# mainboard.net
KiCad netlist of a schematic drawn in EAGLE
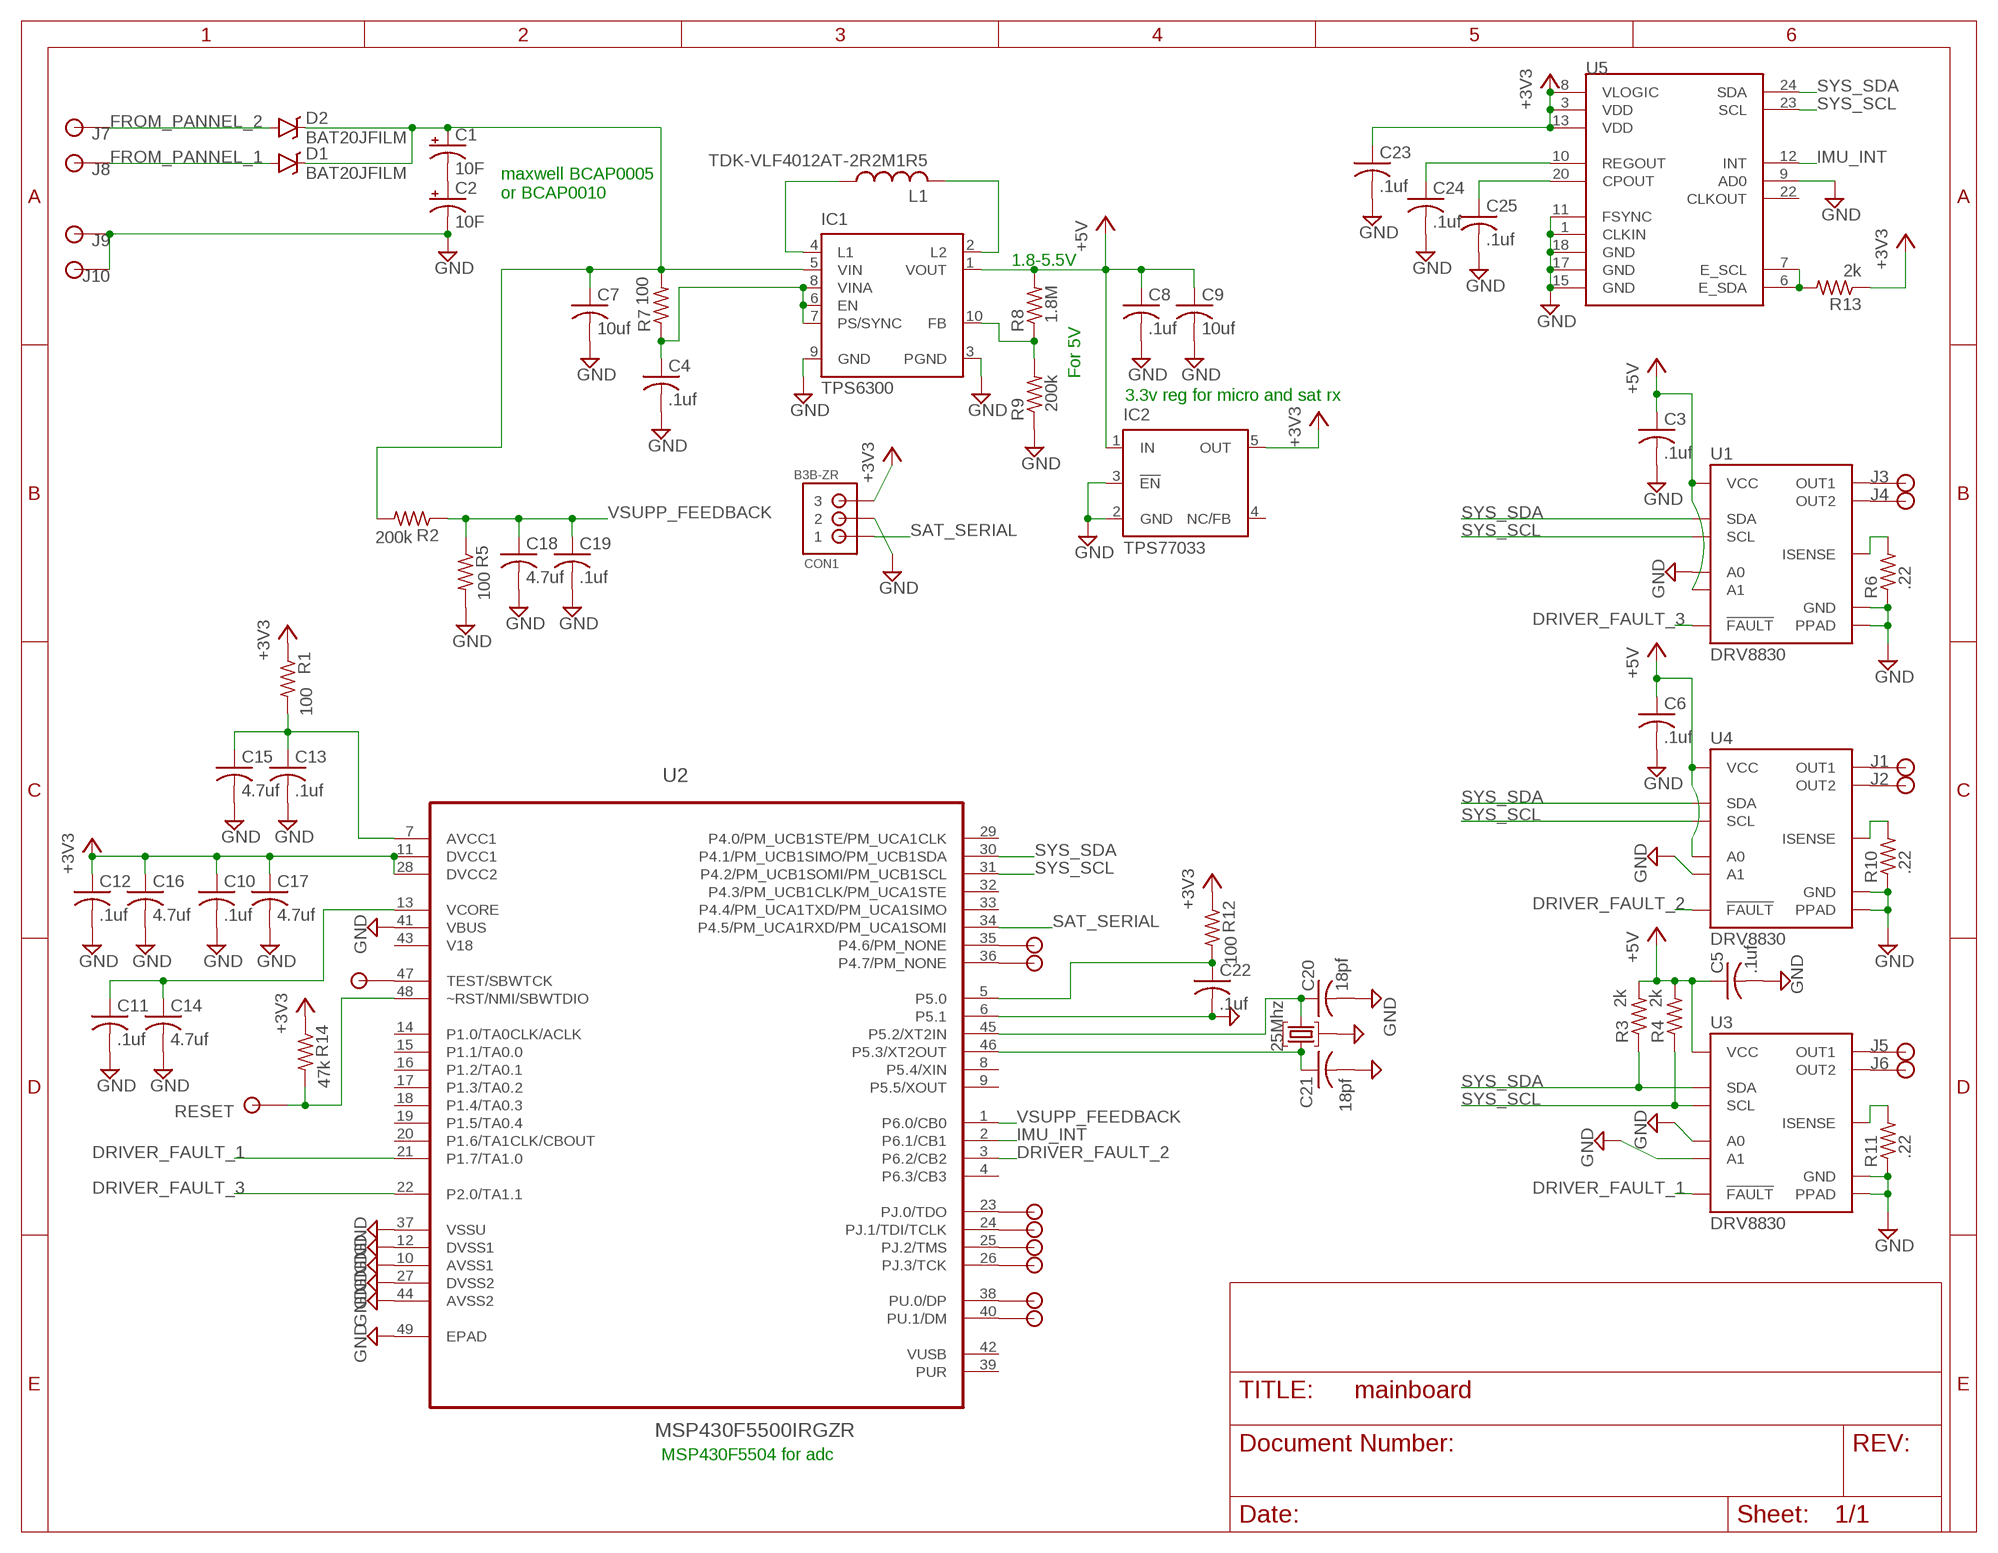
[diagram p0: schematic, sheet 1]

(export (version "E")
  (design (tool "Eeschema 10.0.6"))
  (components
    (comp (ref "C1")
      (value "10F")
      (footprint "eagle-import:E5-10,5")
      (libsource (lib "eagle-import") (part "CPOL-USE5-10.5"))
    )
    (comp (ref "C2")
      (value "10F")
      (footprint "eagle-import:E5-10,5")
      (libsource (lib "eagle-import") (part "CPOL-USE5-10.5"))
    )
    (comp (ref "C3")
      (value ".1uf")
      (footprint "eagle-import:C0603")
      (libsource (lib "eagle-import") (part "C-USC0603"))
    )
    (comp (ref "C4")
      (value ".1uf")
      (footprint "eagle-import:C0603")
      (libsource (lib "eagle-import") (part "C-USC0603"))
    )
    (comp (ref "C5")
      (value ".1uf")
      (footprint "eagle-import:C0603")
      (libsource (lib "eagle-import") (part "C-USC0603"))
    )
    (comp (ref "C6")
      (value ".1uf")
      (footprint "eagle-import:C0603")
      (libsource (lib "eagle-import") (part "C-USC0603"))
    )
    (comp (ref "C7")
      (value "10uf")
      (footprint "eagle-import:C0603")
      (libsource (lib "eagle-import") (part "C-USC0603"))
    )
    (comp (ref "C8")
      (value ".1uf")
      (footprint "eagle-import:C0603")
      (libsource (lib "eagle-import") (part "C-USC0603"))
    )
    (comp (ref "C9")
      (value "10uf")
      (footprint "eagle-import:C0603")
      (libsource (lib "eagle-import") (part "C-USC0603"))
    )
    (comp (ref "C10")
      (value ".1uf")
      (footprint "eagle-import:C0603")
      (libsource (lib "eagle-import") (part "C-USC0603"))
    )
    (comp (ref "C11")
      (value ".1uf")
      (footprint "eagle-import:C0603")
      (libsource (lib "eagle-import") (part "C-USC0603"))
    )
    (comp (ref "C12")
      (value ".1uf")
      (footprint "eagle-import:C0603")
      (libsource (lib "eagle-import") (part "C-USC0603"))
    )
    (comp (ref "C13")
      (value ".1uf")
      (footprint "eagle-import:C0603")
      (libsource (lib "eagle-import") (part "C-USC0603"))
    )
    (comp (ref "C14")
      (value "4.7uf")
      (footprint "eagle-import:C0603")
      (libsource (lib "eagle-import") (part "C-USC0603"))
    )
    (comp (ref "C15")
      (value "4.7uf")
      (footprint "eagle-import:C0603")
      (libsource (lib "eagle-import") (part "C-USC0603"))
    )
    (comp (ref "C16")
      (value "4.7uf")
      (footprint "eagle-import:C0603")
      (libsource (lib "eagle-import") (part "C-USC0603"))
    )
    (comp (ref "C17")
      (value "4.7uf")
      (footprint "eagle-import:C0603")
      (libsource (lib "eagle-import") (part "C-USC0603"))
    )
    (comp (ref "C18")
      (value "4.7uf")
      (footprint "eagle-import:C0603")
      (libsource (lib "eagle-import") (part "C-USC0603"))
    )
    (comp (ref "C19")
      (value ".1uf")
      (footprint "eagle-import:C0603")
      (libsource (lib "eagle-import") (part "C-USC0603"))
    )
    (comp (ref "C20")
      (value "18pf")
      (footprint "eagle-import:C0603")
      (libsource (lib "eagle-import") (part "C-USC0603"))
    )
    (comp (ref "C21")
      (value "18pf")
      (footprint "eagle-import:C0603")
      (libsource (lib "eagle-import") (part "C-USC0603"))
    )
    (comp (ref "C22")
      (value ".1uf")
      (footprint "eagle-import:C0603")
      (libsource (lib "eagle-import") (part "C-USC0603"))
    )
    (comp (ref "C23")
      (value ".1uf")
      (footprint "eagle-import:C0603")
      (libsource (lib "eagle-import") (part "C-USC0603"))
    )
    (comp (ref "C24")
      (value ".1uf")
      (footprint "eagle-import:C0603")
      (libsource (lib "eagle-import") (part "C-USC0603"))
    )
    (comp (ref "C25")
      (value ".1uf")
      (footprint "eagle-import:C0603")
      (libsource (lib "eagle-import") (part "C-USC0603"))
    )
    (comp (ref "CON1")
      (value "B3B-ZR")
      (footprint "eagle-import:B3B-ZR")
      (libsource (lib "eagle-import") (part "B3B-ZR"))
    )
    (comp (ref "D1")
      (value "BAT20JFILM")
      (footprint "eagle-import:SOD-323")
      (libsource (lib "eagle-import") (part "BAT20JFILM"))
    )
    (comp (ref "D2")
      (value "BAT20JFILM")
      (footprint "eagle-import:SOD-323")
      (libsource (lib "eagle-import") (part "BAT20JFILM"))
    )
    (comp (ref "IC1")
      (value "TPS6300")
      (footprint "eagle-import:DRC-S-PVSON-N10")
      (fields (field (name "MPN") "TPS63000DRCTG4"))
      (libsource (lib "eagle-import") (part "TPS6300"))
    )
    (comp (ref "IC2")
      (value "TPS77033")
      (footprint "eagle-import:SOT23-DBV")
      (fields (field (name "MF") "TEXAS INSTRUMENTS") (field (name "MPN") "TPS77033DBVT"))
      (libsource (lib "eagle-import") (part "TPS77033"))
    )
    (comp (ref "J1")
      (value "2MMPAD")
      (footprint "eagle-import:2MMPAD")
      (libsource (lib "eagle-import") (part "2MMPAD"))
    )
    (comp (ref "J2")
      (value "2MMPAD")
      (footprint "eagle-import:2MMPAD")
      (libsource (lib "eagle-import") (part "2MMPAD"))
    )
    (comp (ref "J3")
      (value "2MMPAD")
      (footprint "eagle-import:2MMPAD")
      (libsource (lib "eagle-import") (part "2MMPAD"))
    )
    (comp (ref "J4")
      (value "2MMPAD")
      (footprint "eagle-import:2MMPAD")
      (libsource (lib "eagle-import") (part "2MMPAD"))
    )
    (comp (ref "J5")
      (value "2MMPAD")
      (footprint "eagle-import:2MMPAD")
      (libsource (lib "eagle-import") (part "2MMPAD"))
    )
    (comp (ref "J6")
      (value "2MMPAD")
      (footprint "eagle-import:2MMPAD")
      (libsource (lib "eagle-import") (part "2MMPAD"))
    )
    (comp (ref "J7")
      (value "2MMPAD")
      (footprint "eagle-import:2MMPAD")
      (libsource (lib "eagle-import") (part "2MMPAD"))
    )
    (comp (ref "J8")
      (value "2MMPAD")
      (footprint "eagle-import:2MMPAD")
      (libsource (lib "eagle-import") (part "2MMPAD"))
    )
    (comp (ref "J9")
      (value "2MMPAD")
      (footprint "eagle-import:2MMPAD")
      (libsource (lib "eagle-import") (part "2MMPAD"))
    )
    (comp (ref "J10")
      (value "2MMPAD")
      (footprint "eagle-import:2MMPAD")
      (libsource (lib "eagle-import") (part "2MMPAD"))
    )
    (comp (ref "J11")
      (value "ROUND1MM")
      (footprint "eagle-import:ROUND1MM")
      (libsource (lib "eagle-import") (part "ROUND1MM"))
    )
    (comp (ref "J12")
      (value "ROUND1MM")
      (footprint "eagle-import:ROUND1MM")
      (libsource (lib "eagle-import") (part "ROUND1MM"))
    )
    (comp (ref "J13")
      (value "ROUND1MM")
      (footprint "eagle-import:ROUND1MM")
      (libsource (lib "eagle-import") (part "ROUND1MM"))
    )
    (comp (ref "J14")
      (value "ROUND1MM")
      (footprint "eagle-import:ROUND1MM")
      (libsource (lib "eagle-import") (part "ROUND1MM"))
    )
    (comp (ref "J15")
      (value "ROUND1MM")
      (footprint "eagle-import:ROUND1MM")
      (libsource (lib "eagle-import") (part "ROUND1MM"))
    )
    (comp (ref "J16")
      (value "ROUND1MM")
      (footprint "eagle-import:ROUND1MM")
      (libsource (lib "eagle-import") (part "ROUND1MM"))
    )
    (comp (ref "J17")
      (value "ROUND1MM")
      (footprint "eagle-import:ROUND1MM")
      (libsource (lib "eagle-import") (part "ROUND1MM"))
    )
    (comp (ref "J18")
      (value "ROUND1MM")
      (footprint "eagle-import:ROUND1MM")
      (libsource (lib "eagle-import") (part "ROUND1MM"))
    )
    (comp (ref "J19")
      (value "ROUND1MM")
      (footprint "eagle-import:ROUND1MM")
      (libsource (lib "eagle-import") (part "ROUND1MM"))
    )
    (comp (ref "J20")
      (value "ROUND1MM")
      (footprint "eagle-import:ROUND1MM")
      (libsource (lib "eagle-import") (part "ROUND1MM"))
    )
    (comp (ref "L1")
      (value "TDK-VLF4012AT-2R2M1R5")
      (footprint "eagle-import:TDK-VLF4012AT-2R2M1R5")
      (fields (field (name "MFG") "TDK"))
      (libsource (lib "eagle-import") (part "TDK-VLF4012AT-2R2M1R5"))
    )
    (comp (ref "Q1")
      (value "25Mhz")
      (footprint "eagle-import:SMD-3.2X2.5")
      (libsource (lib "eagle-import") (part "25MHZ-3X2MM"))
    )
    (comp (ref "R1")
      (value "100")
      (footprint "eagle-import:R0402")
      (libsource (lib "eagle-import") (part "R-US_R0402"))
    )
    (comp (ref "R2")
      (value "200k")
      (footprint "eagle-import:R0402")
      (libsource (lib "eagle-import") (part "R-US_R0402"))
    )
    (comp (ref "R3")
      (value "2k")
      (footprint "eagle-import:R0402")
      (libsource (lib "eagle-import") (part "R-US_R0402"))
    )
    (comp (ref "R4")
      (value "2k")
      (footprint "eagle-import:R0402")
      (libsource (lib "eagle-import") (part "R-US_R0402"))
    )
    (comp (ref "R5")
      (value "100")
      (footprint "eagle-import:R0402")
      (libsource (lib "eagle-import") (part "R-US_R0402"))
    )
    (comp (ref "R6")
      (value ".22")
      (footprint "eagle-import:R0402")
      (libsource (lib "eagle-import") (part "R-US_R0402"))
    )
    (comp (ref "R7")
      (value "100")
      (footprint "eagle-import:R0402")
      (libsource (lib "eagle-import") (part "R-US_R0402"))
    )
    (comp (ref "R8")
      (value "1.8M")
      (footprint "eagle-import:R0402")
      (libsource (lib "eagle-import") (part "R-US_R0402"))
    )
    (comp (ref "R9")
      (value "200k")
      (footprint "eagle-import:R0402")
      (libsource (lib "eagle-import") (part "R-US_R0402"))
    )
    (comp (ref "R10")
      (value ".22")
      (footprint "eagle-import:R0402")
      (libsource (lib "eagle-import") (part "R-US_R0402"))
    )
    (comp (ref "R11")
      (value ".22")
      (footprint "eagle-import:R0402")
      (libsource (lib "eagle-import") (part "R-US_R0402"))
    )
    (comp (ref "R12")
      (value "100")
      (footprint "eagle-import:R0402")
      (libsource (lib "eagle-import") (part "R-US_R0402"))
    )
    (comp (ref "R13")
      (value "2k")
      (footprint "eagle-import:R0402")
      (libsource (lib "eagle-import") (part "R-US_R0402"))
    )
    (comp (ref "R14")
      (value "47k")
      (footprint "eagle-import:R0402")
      (libsource (lib "eagle-import") (part "R-US_R0402"))
    )
    (comp (ref "U1")
      (value "DRV8830")
      (footprint "eagle-import:MSOP-10-GNDPAD")
      (libsource (lib "eagle-import") (part "DRV8830"))
    )
    (comp (ref "U2")
      (value "MSP430F5500IRGZR")
      (footprint "eagle-import:QFN50P700X700X100-49N")
      (libsource (lib "eagle-import") (part "MSP430F5500IRGZR"))
    )
    (comp (ref "U3")
      (value "DRV8830")
      (footprint "eagle-import:MSOP-10-GNDPAD")
      (libsource (lib "eagle-import") (part "DRV8830"))
    )
    (comp (ref "U4")
      (value "DRV8830")
      (footprint "eagle-import:MSOP-10-GNDPAD")
      (libsource (lib "eagle-import") (part "DRV8830"))
    )
    (comp (ref "U5")
      (value "MPU-9150QFN-24-NP")
      (footprint "eagle-import:QFN-24-NP")
      (libsource (lib "eagle-import") (part "MPU-9150QFN-24-NP"))
    )
  )
  (nets
    (net (code "1") (name "+3V3") (class "Default")
      (node (ref "C10") (pin "1") (pinfunction "1_1") (pintype "passive"))
      (node (ref "C12") (pin "1") (pinfunction "1_1") (pintype "passive"))
      (node (ref "C16") (pin "1") (pinfunction "1_1") (pintype "passive"))
      (node (ref "C17") (pin "1") (pinfunction "1_1") (pintype "passive"))
      (node (ref "C23") (pin "1") (pinfunction "1_1") (pintype "passive"))
      (node (ref "CON1") (pin "3") (pinfunction "3_3") (pintype "bidirectional"))
      (node (ref "IC2") (pin "5") (pinfunction "OUT_5") (pintype "passive"))
      (node (ref "R1") (pin "1") (pinfunction "1_1") (pintype "passive"))
      (node (ref "R12") (pin "1") (pinfunction "1_1") (pintype "passive"))
      (node (ref "R13") (pin "1") (pinfunction "1_1") (pintype "passive"))
      (node (ref "R14") (pin "1") (pinfunction "1_1") (pintype "passive"))
      (node (ref "U2") (pin "11") (pinfunction "DVCC1_11") (pintype "power_in"))
      (node (ref "U2") (pin "28") (pinfunction "DVCC2_28") (pintype "power_in"))
      (node (ref "U5") (pin "13") (pinfunction "VDD_13") (pintype "bidirectional"))
      (node (ref "U5") (pin "3") (pinfunction "VDD_3") (pintype "bidirectional"))
      (node (ref "U5") (pin "8") (pinfunction "VLOGIC_8") (pintype "bidirectional"))
    )
    (net (code "2") (name "+5V") (class "Default")
      (node (ref "C3") (pin "1") (pinfunction "1_1") (pintype "passive"))
      (node (ref "C5") (pin "1") (pinfunction "1_1") (pintype "passive"))
      (node (ref "C6") (pin "1") (pinfunction "1_1") (pintype "passive"))
      (node (ref "C8") (pin "1") (pinfunction "1_1") (pintype "passive"))
      (node (ref "C9") (pin "1") (pinfunction "1_1") (pintype "passive"))
      (node (ref "IC1") (pin "1") (pinfunction "VOUT_1") (pintype "output"))
      (node (ref "IC2") (pin "1") (pinfunction "IN_1") (pintype "input"))
      (node (ref "R3") (pin "2") (pinfunction "2_2") (pintype "passive"))
      (node (ref "R4") (pin "2") (pinfunction "2_2") (pintype "passive"))
      (node (ref "R8") (pin "2") (pinfunction "2_2") (pintype "passive"))
      (node (ref "U1") (pin "4") (pinfunction "VCC_4") (pintype "power_in"))
      (node (ref "U1") (pin "8") (pinfunction "A1_8") (pintype "input"))
      (node (ref "U3") (pin "4") (pinfunction "VCC_4") (pintype "power_in"))
      (node (ref "U4") (pin "4") (pinfunction "VCC_4") (pintype "power_in"))
      (node (ref "U4") (pin "7") (pinfunction "A0_7") (pintype "input"))
    )
    (net (code "3") (name "/DRIVER_FAULT_1") (class "Default")
      (node (ref "U2") (pin "21") (pinfunction "P1.7/TA1.0_21") (pintype "bidirectional"))
      (node (ref "U3") (pin "6") (pinfunction "~{FAULT}_6") (pintype "output"))
    )
    (net (code "4") (name "/DRIVER_FAULT_2") (class "Default")
      (node (ref "U2") (pin "3") (pinfunction "P6.2/CB2_3") (pintype "bidirectional"))
      (node (ref "U4") (pin "6") (pinfunction "~{FAULT}_6") (pintype "output"))
    )
    (net (code "5") (name "/DRIVER_FAULT_3") (class "Default")
      (node (ref "U1") (pin "6") (pinfunction "~{FAULT}_6") (pintype "output"))
      (node (ref "U2") (pin "22") (pinfunction "P2.0/TA1.1_22") (pintype "bidirectional"))
    )
    (net (code "6") (name "/FROM_PANNEL_1") (class "Default")
      (node (ref "D1") (pin "A") (pinfunction "A_A") (pintype "passive"))
      (node (ref "J8") (pin "P$1") (pinfunction "P$1_P$1") (pintype "bidirectional"))
    )
    (net (code "7") (name "/FROM_PANNEL_2") (class "Default")
      (node (ref "D2") (pin "A") (pinfunction "A_A") (pintype "passive"))
      (node (ref "J7") (pin "P$1") (pinfunction "P$1_P$1") (pintype "bidirectional"))
    )
    (net (code "8") (name "/IMU_INT") (class "Default")
      (node (ref "U2") (pin "2") (pinfunction "P6.1/CB1_2") (pintype "bidirectional"))
      (node (ref "U5") (pin "12") (pinfunction "INT_12") (pintype "bidirectional"))
    )
    (net (code "9") (name "/RESET") (class "Default")
      (node (ref "J15") (pin "P$1") (pinfunction "P$1_P$1") (pintype "bidirectional"))
      (node (ref "R14") (pin "2") (pinfunction "2_2") (pintype "passive"))
      (node (ref "U2") (pin "48") (pinfunction "~{RST/NMI/SBWTDIO}_48") (pintype "bidirectional"))
    )
    (net (code "10") (name "/SAT_SERIAL") (class "Default")
      (node (ref "CON1") (pin "1") (pinfunction "1_1") (pintype "bidirectional"))
      (node (ref "U2") (pin "34") (pinfunction "P4.5/PM_UCA1RXD/PM_UCA1SOMI_34") (pintype "bidirectional"))
    )
    (net (code "11") (name "/SYS_SCL") (class "Default")
      (node (ref "R4") (pin "1") (pinfunction "1_1") (pintype "passive"))
      (node (ref "U1") (pin "10") (pinfunction "SCL_10") (pintype "input"))
      (node (ref "U2") (pin "31") (pinfunction "P4.2/PM_UCB1SOMI/PM_UCB1SCL_31") (pintype "bidirectional"))
      (node (ref "U3") (pin "10") (pinfunction "SCL_10") (pintype "input"))
      (node (ref "U4") (pin "10") (pinfunction "SCL_10") (pintype "input"))
      (node (ref "U5") (pin "23") (pinfunction "SCL_23") (pintype "bidirectional"))
    )
    (net (code "12") (name "/SYS_SDA") (class "Default")
      (node (ref "R3") (pin "1") (pinfunction "1_1") (pintype "passive"))
      (node (ref "U1") (pin "9") (pinfunction "SDA_9") (pintype "bidirectional"))
      (node (ref "U2") (pin "30") (pinfunction "P4.1/PM_UCB1SIMO/PM_UCB1SDA_30") (pintype "bidirectional"))
      (node (ref "U3") (pin "9") (pinfunction "SDA_9") (pintype "bidirectional"))
      (node (ref "U4") (pin "9") (pinfunction "SDA_9") (pintype "bidirectional"))
      (node (ref "U5") (pin "24") (pinfunction "SDA_24") (pintype "bidirectional"))
    )
    (net (code "13") (name "/V18") (class "Default")
      (node (ref "U2") (pin "43") (pinfunction "V18_43") (pintype "power_in"))
    )
    (net (code "14") (name "/VSUPP_FEEDBACK") (class "Default")
      (node (ref "C18") (pin "1") (pinfunction "1_1") (pintype "passive"))
      (node (ref "C19") (pin "1") (pinfunction "1_1") (pintype "passive"))
      (node (ref "R2") (pin "1") (pinfunction "1_1") (pintype "passive"))
      (node (ref "R5") (pin "1") (pinfunction "1_1") (pintype "passive"))
      (node (ref "U2") (pin "1") (pinfunction "P6.0/CB0_1") (pintype "bidirectional"))
    )
    (net (code "15") (name "GND") (class "Default")
      (node (ref "C10") (pin "2") (pinfunction "2_2") (pintype "passive"))
      (node (ref "C11") (pin "2") (pinfunction "2_2") (pintype "passive"))
      (node (ref "C12") (pin "2") (pinfunction "2_2") (pintype "passive"))
      (node (ref "C13") (pin "2") (pinfunction "2_2") (pintype "passive"))
      (node (ref "C14") (pin "2") (pinfunction "2_2") (pintype "passive"))
      (node (ref "C15") (pin "2") (pinfunction "2_2") (pintype "passive"))
      (node (ref "C16") (pin "2") (pinfunction "2_2") (pintype "passive"))
      (node (ref "C17") (pin "2") (pinfunction "2_2") (pintype "passive"))
      (node (ref "C18") (pin "2") (pinfunction "2_2") (pintype "passive"))
      (node (ref "C19") (pin "2") (pinfunction "2_2") (pintype "passive"))
      (node (ref "C2") (pin "-") (pinfunction "-_-") (pintype "passive"))
      (node (ref "C20") (pin "2") (pinfunction "2_2") (pintype "passive"))
      (node (ref "C21") (pin "2") (pinfunction "2_2") (pintype "passive"))
      (node (ref "C22") (pin "2") (pinfunction "2_2") (pintype "passive"))
      (node (ref "C23") (pin "2") (pinfunction "2_2") (pintype "passive"))
      (node (ref "C24") (pin "2") (pinfunction "2_2") (pintype "passive"))
      (node (ref "C25") (pin "2") (pinfunction "2_2") (pintype "passive"))
      (node (ref "C3") (pin "2") (pinfunction "2_2") (pintype "passive"))
      (node (ref "C4") (pin "2") (pinfunction "2_2") (pintype "passive"))
      (node (ref "C5") (pin "2") (pinfunction "2_2") (pintype "passive"))
      (node (ref "C6") (pin "2") (pinfunction "2_2") (pintype "passive"))
      (node (ref "C7") (pin "2") (pinfunction "2_2") (pintype "passive"))
      (node (ref "C8") (pin "2") (pinfunction "2_2") (pintype "passive"))
      (node (ref "C9") (pin "2") (pinfunction "2_2") (pintype "passive"))
      (node (ref "CON1") (pin "2") (pinfunction "2_2") (pintype "bidirectional"))
      (node (ref "IC1") (pin "3") (pinfunction "PGND_3") (pintype "power_in"))
      (node (ref "IC1") (pin "9") (pinfunction "GND_9") (pintype "power_in"))
      (node (ref "IC2") (pin "2") (pinfunction "GND_2") (pintype "power_in"))
      (node (ref "IC2") (pin "3") (pinfunction "~{EN}_3") (pintype "input"))
      (node (ref "J10") (pin "P$1") (pinfunction "P$1_P$1") (pintype "bidirectional"))
      (node (ref "J9") (pin "P$1") (pinfunction "P$1_P$1") (pintype "bidirectional"))
      (node (ref "Q1") (pin "P$2") (pinfunction "2_P$2") (pintype "passive"))
      (node (ref "Q1") (pin "P$4") (pinfunction "2_P$4") (pintype "passive"))
      (node (ref "R10") (pin "1") (pinfunction "1_1") (pintype "passive"))
      (node (ref "R11") (pin "1") (pinfunction "1_1") (pintype "passive"))
      (node (ref "R5") (pin "2") (pinfunction "2_2") (pintype "passive"))
      (node (ref "R6") (pin "1") (pinfunction "1_1") (pintype "passive"))
      (node (ref "R9") (pin "1") (pinfunction "1_1") (pintype "passive"))
      (node (ref "U1") (pin "5") (pinfunction "GND_5") (pintype "power_in"))
      (node (ref "U1") (pin "7") (pinfunction "A0_7") (pintype "input"))
      (node (ref "U1") (pin "GND") (pinfunction "PPAD_GND") (pintype "power_in"))
      (node (ref "U2") (pin "10") (pinfunction "AVSS1_10") (pintype "power_in"))
      (node (ref "U2") (pin "12") (pinfunction "DVSS1_12") (pintype "power_in"))
      (node (ref "U2") (pin "27") (pinfunction "DVSS2_27") (pintype "power_in"))
      (node (ref "U2") (pin "37") (pinfunction "VSSU_37") (pintype "power_in"))
      (node (ref "U2") (pin "41") (pinfunction "VBUS_41") (pintype "input"))
      (node (ref "U2") (pin "44") (pinfunction "AVSS2_44") (pintype "power_in"))
      (node (ref "U2") (pin "49") (pinfunction "EPAD_49") (pintype "passive"))
      (node (ref "U2") (pin "6") (pinfunction "P5.1_6") (pintype "bidirectional"))
      (node (ref "U3") (pin "5") (pinfunction "GND_5") (pintype "power_in"))
      (node (ref "U3") (pin "7") (pinfunction "A0_7") (pintype "input"))
      (node (ref "U3") (pin "8") (pinfunction "A1_8") (pintype "input"))
      (node (ref "U3") (pin "GND") (pinfunction "PPAD_GND") (pintype "power_in"))
      (node (ref "U4") (pin "5") (pinfunction "GND_5") (pintype "power_in"))
      (node (ref "U4") (pin "8") (pinfunction "A1_8") (pintype "input"))
      (node (ref "U4") (pin "GND") (pinfunction "PPAD_GND") (pintype "power_in"))
      (node (ref "U5") (pin "1") (pinfunction "CLKIN_1") (pintype "bidirectional"))
      (node (ref "U5") (pin "11") (pinfunction "FSYNC_11") (pintype "bidirectional"))
      (node (ref "U5") (pin "15") (pinfunction "GND_15") (pintype "bidirectional"))
      (node (ref "U5") (pin "17") (pinfunction "GND_17") (pintype "bidirectional"))
      (node (ref "U5") (pin "18") (pinfunction "GND_18") (pintype "bidirectional"))
      (node (ref "U5") (pin "9") (pinfunction "AD0_9") (pintype "bidirectional"))
    )
    (net (code "16") (name "Net-(C1-Pad-)") (class "Default")
      (node (ref "C1") (pin "-") (pinfunction "-_-") (pintype "passive"))
      (node (ref "C2") (pin "+") (pinfunction "+_+") (pintype "passive"))
    )
    (net (code "17") (name "Net-(IC1A-EN)") (class "Default")
      (node (ref "C4") (pin "1") (pinfunction "1_1") (pintype "passive"))
      (node (ref "IC1") (pin "6") (pinfunction "EN_6") (pintype "input"))
      (node (ref "IC1") (pin "7") (pinfunction "PS/SYNC_7") (pintype "input"))
      (node (ref "IC1") (pin "8") (pinfunction "VINA_8") (pintype "input"))
      (node (ref "R7") (pin "1") (pinfunction "1_1") (pintype "passive"))
    )
    (net (code "18") (name "Net-(IC1A-FB)") (class "Default")
      (node (ref "IC1") (pin "10") (pinfunction "FB_10") (pintype "input"))
      (node (ref "R8") (pin "1") (pinfunction "1_1") (pintype "passive"))
      (node (ref "R9") (pin "2") (pinfunction "2_2") (pintype "passive"))
    )
    (net (code "19") (name "Net-(IC1A-L1)") (class "Default")
      (node (ref "IC1") (pin "4") (pinfunction "L1_4") (pintype "passive"))
      (node (ref "L1") (pin "P$1") (pinfunction "1_P$1") (pintype "passive"))
    )
    (net (code "20") (name "Net-(IC1A-L2)") (class "Default")
      (node (ref "IC1") (pin "2") (pinfunction "L2_2") (pintype "passive"))
      (node (ref "L1") (pin "P$2") (pinfunction "2_P$2") (pintype "passive"))
    )
    (net (code "21") (name "Net-(IC1A-VIN)") (class "Default")
      (node (ref "C1") (pin "+") (pinfunction "+_+") (pintype "passive"))
      (node (ref "C7") (pin "1") (pinfunction "1_1") (pintype "passive"))
      (node (ref "D1") (pin "C") (pinfunction "C_C") (pintype "passive"))
      (node (ref "D2") (pin "C") (pinfunction "C_C") (pintype "passive"))
      (node (ref "IC1") (pin "5") (pinfunction "VIN_5") (pintype "input"))
      (node (ref "R2") (pin "2") (pinfunction "2_2") (pintype "passive"))
      (node (ref "R7") (pin "2") (pinfunction "2_2") (pintype "passive"))
    )
    (net (code "22") (name "Net-(Q1-1)") (class "Default")
      (node (ref "C21") (pin "1") (pinfunction "1_1") (pintype "passive"))
      (node (ref "Q1") (pin "P$3") (pinfunction "1_P$3") (pintype "passive"))
      (node (ref "U2") (pin "46") (pinfunction "P5.3/XT2OUT_46") (pintype "bidirectional"))
    )
    (net (code "23") (name "Net-(Q1-3)") (class "Default")
      (node (ref "C20") (pin "1") (pinfunction "1_1") (pintype "passive"))
      (node (ref "Q1") (pin "P$1") (pinfunction "3_P$1") (pintype "passive"))
      (node (ref "U2") (pin "45") (pinfunction "P5.2/XT2IN_45") (pintype "bidirectional"))
    )
    (net (code "24") (name "Net-(U1-ISENSE)") (class "Default")
      (node (ref "R6") (pin "2") (pinfunction "2_2") (pintype "passive"))
      (node (ref "U1") (pin "2") (pinfunction "ISENSE_2") (pintype "bidirectional"))
    )
    (net (code "25") (name "Net-(U1-OUT1)") (class "Default")
      (node (ref "J3") (pin "P$1") (pinfunction "P$1_P$1") (pintype "bidirectional"))
      (node (ref "U1") (pin "3") (pinfunction "OUT1_3") (pintype "power_in"))
    )
    (net (code "26") (name "Net-(U1-OUT2)") (class "Default")
      (node (ref "J4") (pin "P$1") (pinfunction "P$1_P$1") (pintype "bidirectional"))
      (node (ref "U1") (pin "1") (pinfunction "OUT2_1") (pintype "power_in"))
    )
    (net (code "27") (name "Net-(U2-AVCC1)") (class "Default")
      (node (ref "C13") (pin "1") (pinfunction "1_1") (pintype "passive"))
      (node (ref "C15") (pin "1") (pinfunction "1_1") (pintype "passive"))
      (node (ref "R1") (pin "2") (pinfunction "2_2") (pintype "passive"))
      (node (ref "U2") (pin "7") (pinfunction "AVCC1_7") (pintype "power_in"))
    )
    (net (code "28") (name "Net-(U2-P4.6{slash}PM_NONE)") (class "Default")
      (node (ref "J18") (pin "P$1") (pinfunction "P$1_P$1") (pintype "bidirectional"))
      (node (ref "U2") (pin "35") (pinfunction "P4.6/PM_NONE_35") (pintype "bidirectional"))
    )
    (net (code "29") (name "Net-(U2-P4.7{slash}PM_NONE)") (class "Default")
      (node (ref "J17") (pin "P$1") (pinfunction "P$1_P$1") (pintype "bidirectional"))
      (node (ref "U2") (pin "36") (pinfunction "P4.7/PM_NONE_36") (pintype "bidirectional"))
    )
    (net (code "30") (name "Net-(U2-P5.0)") (class "Default")
      (node (ref "C22") (pin "1") (pinfunction "1_1") (pintype "passive"))
      (node (ref "R12") (pin "2") (pinfunction "2_2") (pintype "passive"))
      (node (ref "U2") (pin "5") (pinfunction "P5.0_5") (pintype "bidirectional"))
    )
    (net (code "31") (name "Net-(U2-PJ.0{slash}TDO)") (class "Default")
      (node (ref "J11") (pin "P$1") (pinfunction "P$1_P$1") (pintype "bidirectional"))
      (node (ref "U2") (pin "23") (pinfunction "PJ.0/TDO_23") (pintype "bidirectional"))
    )
    (net (code "32") (name "Net-(U2-PJ.1{slash}TDI{slash}TCLK)") (class "Default")
      (node (ref "J12") (pin "P$1") (pinfunction "P$1_P$1") (pintype "bidirectional"))
      (node (ref "U2") (pin "24") (pinfunction "PJ.1/TDI/TCLK_24") (pintype "bidirectional"))
    )
    (net (code "33") (name "Net-(U2-PJ.2{slash}TMS)") (class "Default")
      (node (ref "J13") (pin "P$1") (pinfunction "P$1_P$1") (pintype "bidirectional"))
      (node (ref "U2") (pin "25") (pinfunction "PJ.2/TMS_25") (pintype "bidirectional"))
    )
    (net (code "34") (name "Net-(U2-PJ.3{slash}TCK)") (class "Default")
      (node (ref "J14") (pin "P$1") (pinfunction "P$1_P$1") (pintype "bidirectional"))
      (node (ref "U2") (pin "26") (pinfunction "PJ.3/TCK_26") (pintype "bidirectional"))
    )
    (net (code "35") (name "Net-(U2-PU.0{slash}DP)") (class "Default")
      (node (ref "J19") (pin "P$1") (pinfunction "P$1_P$1") (pintype "bidirectional"))
      (node (ref "U2") (pin "38") (pinfunction "PU.0/DP_38") (pintype "bidirectional"))
    )
    (net (code "36") (name "Net-(U2-PU.1{slash}DM)") (class "Default")
      (node (ref "J20") (pin "P$1") (pinfunction "P$1_P$1") (pintype "bidirectional"))
      (node (ref "U2") (pin "40") (pinfunction "PU.1/DM_40") (pintype "bidirectional"))
    )
    (net (code "37") (name "Net-(U2-TEST{slash}SBWTCK)") (class "Default")
      (node (ref "J16") (pin "P$1") (pinfunction "P$1_P$1") (pintype "bidirectional"))
      (node (ref "U2") (pin "47") (pinfunction "TEST/SBWTCK_47") (pintype "input"))
    )
    (net (code "38") (name "Net-(U2-VCORE)") (class "Default")
      (node (ref "C11") (pin "1") (pinfunction "1_1") (pintype "passive"))
      (node (ref "C14") (pin "1") (pinfunction "1_1") (pintype "passive"))
      (node (ref "U2") (pin "13") (pinfunction "VCORE_13") (pintype "power_in"))
    )
    (net (code "39") (name "Net-(U3-ISENSE)") (class "Default")
      (node (ref "R11") (pin "2") (pinfunction "2_2") (pintype "passive"))
      (node (ref "U3") (pin "2") (pinfunction "ISENSE_2") (pintype "bidirectional"))
    )
    (net (code "40") (name "Net-(U3-OUT1)") (class "Default")
      (node (ref "J5") (pin "P$1") (pinfunction "P$1_P$1") (pintype "bidirectional"))
      (node (ref "U3") (pin "3") (pinfunction "OUT1_3") (pintype "power_in"))
    )
    (net (code "41") (name "Net-(U3-OUT2)") (class "Default")
      (node (ref "J6") (pin "P$1") (pinfunction "P$1_P$1") (pintype "bidirectional"))
      (node (ref "U3") (pin "1") (pinfunction "OUT2_1") (pintype "power_in"))
    )
    (net (code "42") (name "Net-(U4-ISENSE)") (class "Default")
      (node (ref "R10") (pin "2") (pinfunction "2_2") (pintype "passive"))
      (node (ref "U4") (pin "2") (pinfunction "ISENSE_2") (pintype "bidirectional"))
    )
    (net (code "43") (name "Net-(U4-OUT1)") (class "Default")
      (node (ref "J1") (pin "P$1") (pinfunction "P$1_P$1") (pintype "bidirectional"))
      (node (ref "U4") (pin "3") (pinfunction "OUT1_3") (pintype "power_in"))
    )
    (net (code "44") (name "Net-(U4-OUT2)") (class "Default")
      (node (ref "J2") (pin "P$1") (pinfunction "P$1_P$1") (pintype "bidirectional"))
      (node (ref "U4") (pin "1") (pinfunction "OUT2_1") (pintype "power_in"))
    )
    (net (code "45") (name "Net-(U5-CPOUT)") (class "Default")
      (node (ref "C25") (pin "1") (pinfunction "1_1") (pintype "passive"))
      (node (ref "U5") (pin "20") (pinfunction "CPOUT_20") (pintype "bidirectional"))
    )
    (net (code "46") (name "Net-(U5-E_SCL)") (class "Default")
      (node (ref "R13") (pin "2") (pinfunction "2_2") (pintype "passive"))
      (node (ref "U5") (pin "6") (pinfunction "E_SDA_6") (pintype "bidirectional"))
      (node (ref "U5") (pin "7") (pinfunction "E_SCL_7") (pintype "bidirectional"))
    )
    (net (code "47") (name "Net-(U5-REGOUT)") (class "Default")
      (node (ref "C24") (pin "1") (pinfunction "1_1") (pintype "passive"))
      (node (ref "U5") (pin "10") (pinfunction "REGOUT_10") (pintype "bidirectional"))
    )
    (net (code "48") (name "unconnected-(IC2-NC{slash}FB-Pad4)") (class "Default")
      (node (ref "IC2") (pin "4") (pinfunction "NC/FB_4") (pintype "passive"))
    )
    (net (code "49") (name "unconnected-(U2-P1.0{slash}TA0CLK{slash}ACLK-Pad14)") (class "Default")
      (node (ref "U2") (pin "14") (pinfunction "P1.0/TA0CLK/ACLK_14") (pintype "bidirectional"))
    )
    (net (code "50") (name "unconnected-(U2-P1.1{slash}TA0.0-Pad15)") (class "Default")
      (node (ref "U2") (pin "15") (pinfunction "P1.1/TA0.0_15") (pintype "bidirectional"))
    )
    (net (code "51") (name "unconnected-(U2-P1.2{slash}TA0.1-Pad16)") (class "Default")
      (node (ref "U2") (pin "16") (pinfunction "P1.2/TA0.1_16") (pintype "bidirectional"))
    )
    (net (code "52") (name "unconnected-(U2-P1.3{slash}TA0.2-Pad17)") (class "Default")
      (node (ref "U2") (pin "17") (pinfunction "P1.3/TA0.2_17") (pintype "bidirectional"))
    )
    (net (code "53") (name "unconnected-(U2-P1.4{slash}TA0.3-Pad18)") (class "Default")
      (node (ref "U2") (pin "18") (pinfunction "P1.4/TA0.3_18") (pintype "bidirectional"))
    )
    (net (code "54") (name "unconnected-(U2-P1.5{slash}TA0.4-Pad19)") (class "Default")
      (node (ref "U2") (pin "19") (pinfunction "P1.5/TA0.4_19") (pintype "bidirectional"))
    )
    (net (code "55") (name "unconnected-(U2-P1.6{slash}TA1CLK{slash}CBOUT-Pad20)") (class "Default")
      (node (ref "U2") (pin "20") (pinfunction "P1.6/TA1CLK/CBOUT_20") (pintype "bidirectional"))
    )
    (net (code "56") (name "unconnected-(U2-P4.0{slash}PM_UCB1STE{slash}PM_UCA1CLK-Pad29)") (class "Default")
      (node (ref "U2") (pin "29") (pinfunction "P4.0/PM_UCB1STE/PM_UCA1CLK_29") (pintype "bidirectional"))
    )
    (net (code "57") (name "unconnected-(U2-P4.3{slash}PM_UCB1CLK{slash}PM_UCA1STE-Pad32)") (class "Default")
      (node (ref "U2") (pin "32") (pinfunction "P4.3/PM_UCB1CLK/PM_UCA1STE_32") (pintype "bidirectional"))
    )
    (net (code "58") (name "unconnected-(U2-P4.4{slash}PM_UCA1TXD{slash}PM_UCA1SIMO-Pad33)") (class "Default")
      (node (ref "U2") (pin "33") (pinfunction "P4.4/PM_UCA1TXD/PM_UCA1SIMO_33") (pintype "bidirectional"))
    )
    (net (code "59") (name "unconnected-(U2-P5.4{slash}XIN-Pad8)") (class "Default")
      (node (ref "U2") (pin "8") (pinfunction "P5.4/XIN_8") (pintype "bidirectional"))
    )
    (net (code "60") (name "unconnected-(U2-P5.5{slash}XOUT-Pad9)") (class "Default")
      (node (ref "U2") (pin "9") (pinfunction "P5.5/XOUT_9") (pintype "bidirectional"))
    )
    (net (code "61") (name "unconnected-(U2-P6.3{slash}CB3-Pad4)") (class "Default")
      (node (ref "U2") (pin "4") (pinfunction "P6.3/CB3_4") (pintype "bidirectional"))
    )
    (net (code "62") (name "unconnected-(U2-PUR-Pad39)") (class "Default")
      (node (ref "U2") (pin "39") (pinfunction "PUR_39") (pintype "bidirectional"))
    )
    (net (code "63") (name "unconnected-(U2-VUSB-Pad42)") (class "Default")
      (node (ref "U2") (pin "42") (pinfunction "VUSB_42") (pintype "output"))
    )
    (net (code "64") (name "unconnected-(U5-CLKOUT-Pad22)") (class "Default")
      (node (ref "U5") (pin "22") (pinfunction "CLKOUT_22") (pintype "bidirectional"))
    )
  )
)
